# FSStation.net
KiCad netlist of a schematic drawn in EAGLE
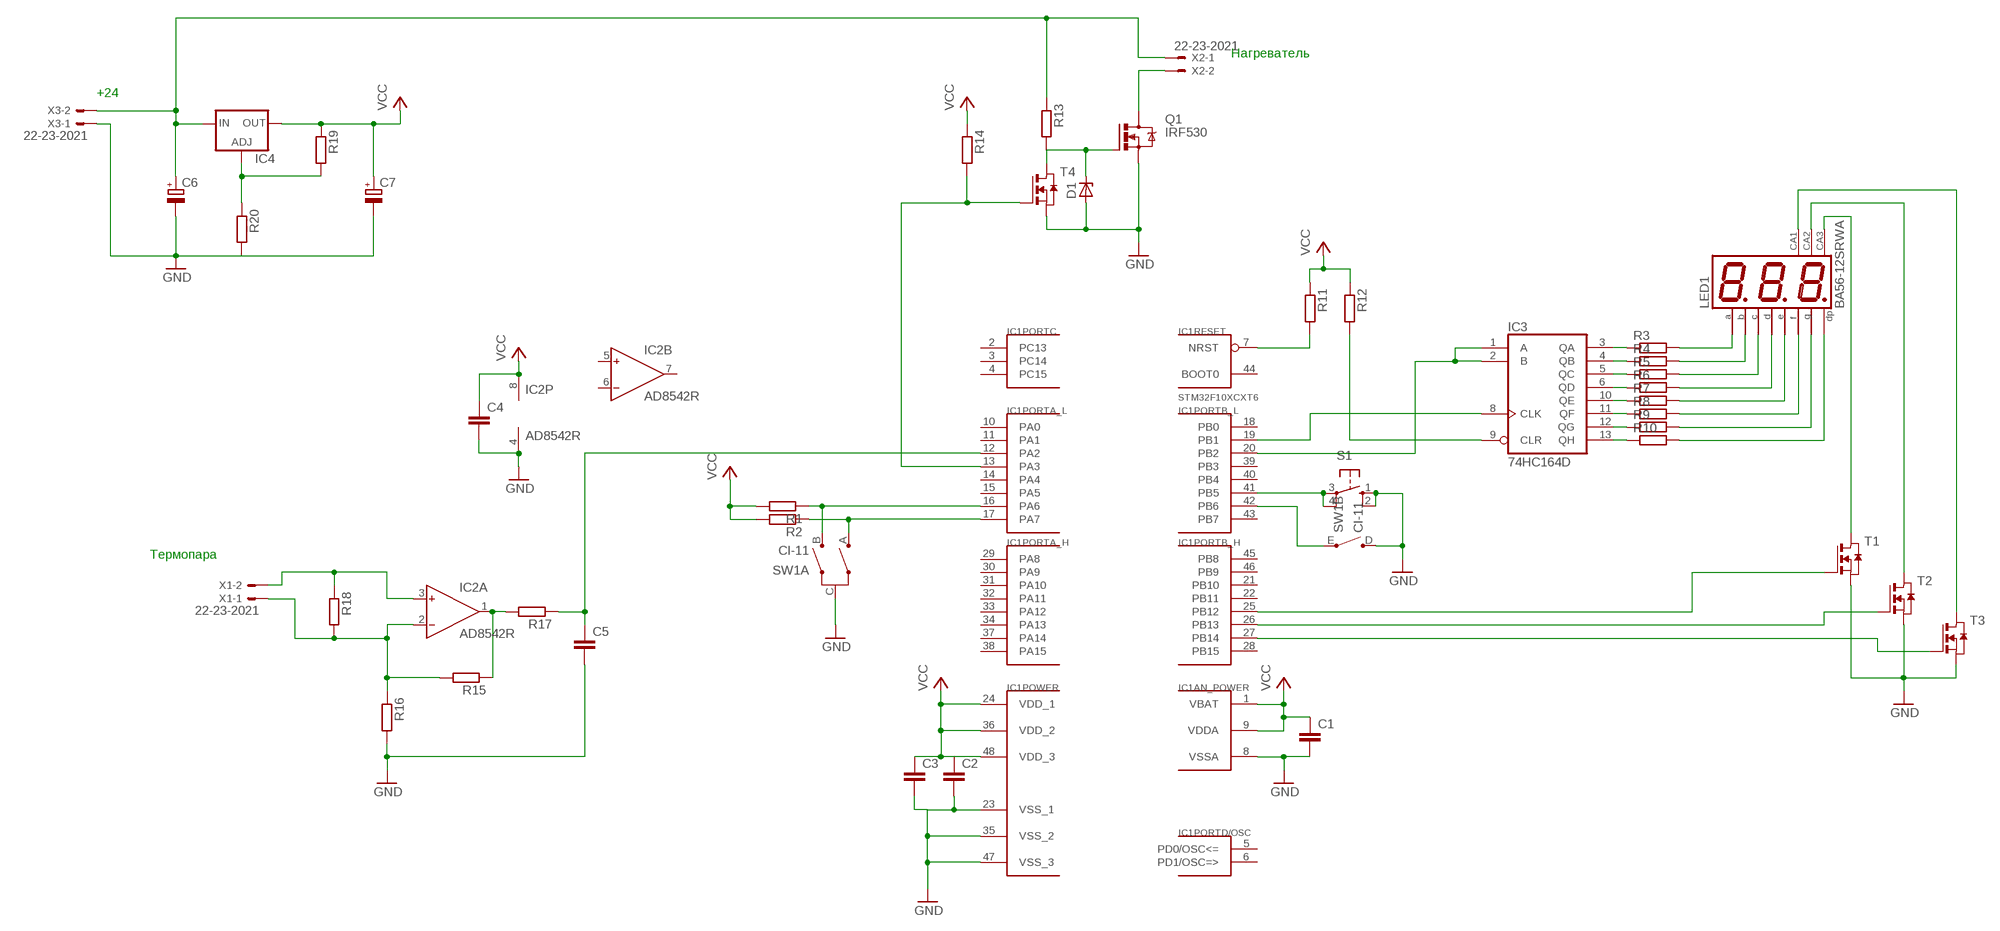
[diagram p0: schematic, sheet 1]

(export (version "E")
  (design (tool "Eeschema 10.0.6"))
  (components
    (comp (ref "C1")
      (value "C-EUC0805")
      (footprint "eagle-import:C0805")
      (libsource (lib "eagle-import") (part "C-EUC0805"))
    )
    (comp (ref "C2")
      (value "C-EUC0805")
      (footprint "eagle-import:C0805")
      (libsource (lib "eagle-import") (part "C-EUC0805"))
    )
    (comp (ref "C3")
      (value "C-EUC0805")
      (footprint "eagle-import:C0805")
      (libsource (lib "eagle-import") (part "C-EUC0805"))
    )
    (comp (ref "C4")
      (value "C-EUC0805")
      (footprint "eagle-import:C0805")
      (libsource (lib "eagle-import") (part "C-EUC0805"))
    )
    (comp (ref "C5")
      (value "C-EUC0805")
      (footprint "eagle-import:C0805")
      (libsource (lib "eagle-import") (part "C-EUC0805"))
    )
    (comp (ref "C6")
      (value "CPOL-EUE2.5-5")
      (footprint "eagle-import:E2,5-5")
      (libsource (lib "eagle-import") (part "CPOL-EUE2.5-5"))
    )
    (comp (ref "C7")
      (value "CPOL-EUE2.5-5")
      (footprint "eagle-import:E2,5-5")
      (libsource (lib "eagle-import") (part "CPOL-EUE2.5-5"))
    )
    (comp (ref "D1")
      (value "ZENER-DIODEDO34-7")
      (footprint "eagle-import:DO34Z7")
      (libsource (lib "eagle-import") (part "ZENER-DIODEDO34-7"))
    )
    (comp (ref "IC1")
      (value "STM32F10XCXT6")
      (footprint "eagle-import:TQFP48")
      (libsource (lib "eagle-import") (part "STM32F10XCXT6"))
    )
    (comp (ref "IC2")
      (value "AD8542R")
      (footprint "eagle-import:SO8")
      (fields (field (name "MF") "ALTERA CORPORATION") (field (name "MPN") "AD8542ARZ-REEL"))
      (libsource (lib "eagle-import") (part "AD8542R"))
    )
    (comp (ref "IC3")
      (value "74HC164D")
      (footprint "eagle-import:SO14")
      (libsource (lib "eagle-import") (part "74164DHC"))
    )
    (comp (ref "IC4")
      (value "LM317TS")
      (footprint "eagle-import:317TS")
      (libsource (lib "eagle-import") (part "LM317TS"))
    )
    (comp (ref "LED1")
      (value "BA56-12SRWA")
      (footprint "eagle-import:BX56-12")
      (libsource (lib "eagle-import") (part "B?56-12WAASR"))
    )
    (comp (ref "Q1")
      (value "IRF530")
      (footprint "eagle-import:TO220BV")
      (libsource (lib "eagle-import") (part "IRF530"))
    )
    (comp (ref "R1")
      (value "R-EU_R0805")
      (footprint "eagle-import:R0805")
      (libsource (lib "eagle-import") (part "R-EU_R0805"))
    )
    (comp (ref "R2")
      (value "R-EU_R0805")
      (footprint "eagle-import:R0805")
      (libsource (lib "eagle-import") (part "R-EU_R0805"))
    )
    (comp (ref "R3")
      (value "R-EU_R0805")
      (footprint "eagle-import:R0805")
      (libsource (lib "eagle-import") (part "R-EU_R0805"))
    )
    (comp (ref "R4")
      (value "R-EU_R0805")
      (footprint "eagle-import:R0805")
      (libsource (lib "eagle-import") (part "R-EU_R0805"))
    )
    (comp (ref "R5")
      (value "R-EU_R0805")
      (footprint "eagle-import:R0805")
      (libsource (lib "eagle-import") (part "R-EU_R0805"))
    )
    (comp (ref "R6")
      (value "R-EU_R0805")
      (footprint "eagle-import:R0805")
      (libsource (lib "eagle-import") (part "R-EU_R0805"))
    )
    (comp (ref "R7")
      (value "R-EU_R0805")
      (footprint "eagle-import:R0805")
      (libsource (lib "eagle-import") (part "R-EU_R0805"))
    )
    (comp (ref "R8")
      (value "R-EU_R0805")
      (footprint "eagle-import:R0805")
      (libsource (lib "eagle-import") (part "R-EU_R0805"))
    )
    (comp (ref "R9")
      (value "R-EU_R0805")
      (footprint "eagle-import:R0805")
      (libsource (lib "eagle-import") (part "R-EU_R0805"))
    )
    (comp (ref "R10")
      (value "R-EU_R0805")
      (footprint "eagle-import:R0805")
      (libsource (lib "eagle-import") (part "R-EU_R0805"))
    )
    (comp (ref "R11")
      (value "R-EU_R0805")
      (footprint "eagle-import:R0805")
      (libsource (lib "eagle-import") (part "R-EU_R0805"))
    )
    (comp (ref "R12")
      (value "R-EU_R0805")
      (footprint "eagle-import:R0805")
      (libsource (lib "eagle-import") (part "R-EU_R0805"))
    )
    (comp (ref "R13")
      (value "R-EU_R0805")
      (footprint "eagle-import:R0805")
      (libsource (lib "eagle-import") (part "R-EU_R0805"))
    )
    (comp (ref "R14")
      (value "R-EU_R0805")
      (footprint "eagle-import:R0805")
      (libsource (lib "eagle-import") (part "R-EU_R0805"))
    )
    (comp (ref "R15")
      (value "R-EU_R0805")
      (footprint "eagle-import:R0805")
      (libsource (lib "eagle-import") (part "R-EU_R0805"))
    )
    (comp (ref "R16")
      (value "R-EU_R0805")
      (footprint "eagle-import:R0805")
      (libsource (lib "eagle-import") (part "R-EU_R0805"))
    )
    (comp (ref "R17")
      (value "R-EU_R0805")
      (footprint "eagle-import:R0805")
      (libsource (lib "eagle-import") (part "R-EU_R0805"))
    )
    (comp (ref "R18")
      (value "R-EU_R0805")
      (footprint "eagle-import:R0805")
      (libsource (lib "eagle-import") (part "R-EU_R0805"))
    )
    (comp (ref "R19")
      (value "R-EU_R0805")
      (footprint "eagle-import:R0805")
      (libsource (lib "eagle-import") (part "R-EU_R0805"))
    )
    (comp (ref "R20")
      (value "R-EU_R0805")
      (footprint "eagle-import:R0805")
      (libsource (lib "eagle-import") (part "R-EU_R0805"))
    )
    (comp (ref "S1")
      (value "40-XX")
      (footprint "eagle-import:B3F-40XX")
      (fields (field (name "MF") "OMRON COMPONENTS USA") (field (name "MPN") "B3F-4000"))
      (libsource (lib "eagle-import") (part "40-XX"))
    )
    (comp (ref "SW1")
      (value "CI-11")
      (footprint "eagle-import:CI-11")
      (libsource (lib "eagle-import") (part "CI-11"))
    )
    (comp (ref "T1")
      (value "NMOSSOT23")
      (footprint "eagle-import:SOT-23")
      (libsource (lib "eagle-import") (part "NMOSSOT23"))
    )
    (comp (ref "T2")
      (value "NMOSSOT23")
      (footprint "eagle-import:SOT-23")
      (libsource (lib "eagle-import") (part "NMOSSOT23"))
    )
    (comp (ref "T3")
      (value "NMOSSOT23")
      (footprint "eagle-import:SOT-23")
      (libsource (lib "eagle-import") (part "NMOSSOT23"))
    )
    (comp (ref "T4")
      (value "NMOSSOT23")
      (footprint "eagle-import:SOT-23")
      (libsource (lib "eagle-import") (part "NMOSSOT23"))
    )
    (comp (ref "X1")
      (value "22-23-2021")
      (footprint "eagle-import:22-23-2021")
      (fields (field (name "MF") "MOLEX"))
      (libsource (lib "eagle-import") (part "22-23-2021"))
    )
    (comp (ref "X2")
      (value "22-23-2021")
      (footprint "eagle-import:22-23-2021")
      (fields (field (name "MF") "MOLEX"))
      (libsource (lib "eagle-import") (part "22-23-2021"))
    )
    (comp (ref "X3")
      (value "22-23-2021")
      (footprint "eagle-import:22-23-2021")
      (fields (field (name "MF") "MOLEX"))
      (libsource (lib "eagle-import") (part "22-23-2021"))
    )
  )
  (nets
    (net (code "1") (name "GND") (class "Default")
      (node (ref "C1") (pin "2") (pinfunction "2_2") (pintype "passive"))
      (node (ref "C2") (pin "2") (pinfunction "2_2") (pintype "passive"))
      (node (ref "C3") (pin "2") (pinfunction "2_2") (pintype "passive"))
      (node (ref "C4") (pin "2") (pinfunction "2_2") (pintype "passive"))
      (node (ref "C5") (pin "2") (pinfunction "2_2") (pintype "passive"))
      (node (ref "C6") (pin "-") (pinfunction "-_-") (pintype "passive"))
      (node (ref "C7") (pin "-") (pinfunction "-_-") (pintype "passive"))
      (node (ref "D1") (pin "A") (pinfunction "A_A") (pintype "passive"))
      (node (ref "IC1") (pin "23") (pinfunction "VSS_1_23") (pintype "power_in"))
      (node (ref "IC1") (pin "35") (pinfunction "VSS_2_35") (pintype "power_in"))
      (node (ref "IC1") (pin "47") (pinfunction "VSS_3_47") (pintype "power_in"))
      (node (ref "IC1") (pin "8") (pinfunction "VSSA_8") (pintype "power_in"))
      (node (ref "IC2") (pin "4") (pinfunction "V-_4") (pintype "power_in"))
      (node (ref "Q1") (pin "S") (pinfunction "S_S") (pintype "passive"))
      (node (ref "R16") (pin "2") (pinfunction "2_2") (pintype "passive"))
      (node (ref "R20") (pin "2") (pinfunction "2_2") (pintype "passive"))
      (node (ref "S1") (pin "1") (pinfunction "S_1") (pintype "passive"))
      (node (ref "S1") (pin "2") (pinfunction "S1_2") (pintype "passive"))
      (node (ref "SW1") (pin "C") (pinfunction "C_C") (pintype "passive"))
      (node (ref "SW1") (pin "D") (pinfunction "D_D") (pintype "passive"))
      (node (ref "T1") (pin "2") (pinfunction "S_2") (pintype "passive"))
      (node (ref "T2") (pin "2") (pinfunction "S_2") (pintype "passive"))
      (node (ref "T3") (pin "2") (pinfunction "S_2") (pintype "passive"))
      (node (ref "T4") (pin "2") (pinfunction "S_2") (pintype "passive"))
      (node (ref "X3") (pin "1") (pinfunction "S_1") (pintype "passive"))
    )
    (net (code "2") (name "Net-(IC1C-PA2)") (class "Default")
      (node (ref "C5") (pin "1") (pinfunction "1_1") (pintype "passive"))
      (node (ref "IC1") (pin "12") (pinfunction "PA2_12") (pintype "bidirectional"))
      (node (ref "R17") (pin "1") (pinfunction "1_1") (pintype "passive"))
    )
    (net (code "3") (name "Net-(IC1C-PA3)") (class "Default")
      (node (ref "IC1") (pin "13") (pinfunction "PA3_13") (pintype "bidirectional"))
      (node (ref "R14") (pin "2") (pinfunction "2_2") (pintype "passive"))
      (node (ref "T4") (pin "3") (pinfunction "G_3") (pintype "passive"))
    )
    (net (code "4") (name "Net-(IC1C-PA6)") (class "Default")
      (node (ref "IC1") (pin "16") (pinfunction "PA6_16") (pintype "bidirectional"))
      (node (ref "R1") (pin "1") (pinfunction "1_1") (pintype "passive"))
      (node (ref "SW1") (pin "B") (pinfunction "B_B") (pintype "passive"))
    )
    (net (code "5") (name "Net-(IC1C-PA7)") (class "Default")
      (node (ref "IC1") (pin "17") (pinfunction "PA7_17") (pintype "bidirectional"))
      (node (ref "R2") (pin "1") (pinfunction "1_1") (pintype "passive"))
      (node (ref "SW1") (pin "A") (pinfunction "A_A") (pintype "passive"))
    )
    (net (code "6") (name "Net-(IC1D-PB12)") (class "Default")
      (node (ref "IC1") (pin "25") (pinfunction "PB12_25") (pintype "bidirectional"))
      (node (ref "T1") (pin "3") (pinfunction "G_3") (pintype "passive"))
    )
    (net (code "7") (name "Net-(IC1D-PB13)") (class "Default")
      (node (ref "IC1") (pin "26") (pinfunction "PB13_26") (pintype "bidirectional"))
      (node (ref "T2") (pin "3") (pinfunction "G_3") (pintype "passive"))
    )
    (net (code "8") (name "Net-(IC1D-PB14)") (class "Default")
      (node (ref "IC1") (pin "27") (pinfunction "PB14_27") (pintype "bidirectional"))
      (node (ref "T3") (pin "3") (pinfunction "G_3") (pintype "passive"))
    )
    (net (code "9") (name "Net-(IC1E-PB1)") (class "Default")
      (node (ref "IC1") (pin "19") (pinfunction "PB1_19") (pintype "bidirectional"))
      (node (ref "IC3") (pin "8") (pinfunction "CLK_8") (pintype "input"))
    )
    (net (code "10") (name "Net-(IC1E-PB2)") (class "Default")
      (node (ref "IC1") (pin "20") (pinfunction "PB2_20") (pintype "bidirectional"))
      (node (ref "IC3") (pin "1") (pinfunction "A_1") (pintype "input"))
      (node (ref "IC3") (pin "2") (pinfunction "B_2") (pintype "input"))
    )
    (net (code "11") (name "Net-(IC1E-PB5)") (class "Default")
      (node (ref "IC1") (pin "41") (pinfunction "PB5_41") (pintype "bidirectional"))
      (node (ref "S1") (pin "3") (pinfunction "P_3") (pintype "passive"))
      (node (ref "S1") (pin "4") (pinfunction "P1_4") (pintype "passive"))
    )
    (net (code "12") (name "Net-(IC1E-PB6)") (class "Default")
      (node (ref "IC1") (pin "42") (pinfunction "PB6_42") (pintype "bidirectional"))
      (node (ref "SW1") (pin "E") (pinfunction "E_E") (pintype "passive"))
    )
    (net (code "13") (name "Net-(IC1I-NRST)") (class "Default")
      (node (ref "IC1") (pin "7") (pinfunction "NRST_7") (pintype "input"))
      (node (ref "R11") (pin "2") (pinfunction "2_2") (pintype "passive"))
    )
    (net (code "14") (name "Net-(IC2A-IN+)") (class "Default")
      (node (ref "IC2") (pin "3") (pinfunction "IN+_3") (pintype "input"))
      (node (ref "R18") (pin "1") (pinfunction "1_1") (pintype "passive"))
      (node (ref "X1") (pin "2") (pinfunction "S_2") (pintype "passive"))
    )
    (net (code "15") (name "Net-(IC2A-IN-)") (class "Default")
      (node (ref "IC2") (pin "2") (pinfunction "IN-_2") (pintype "input"))
      (node (ref "R15") (pin "2") (pinfunction "2_2") (pintype "passive"))
      (node (ref "R16") (pin "1") (pinfunction "1_1") (pintype "passive"))
      (node (ref "R18") (pin "2") (pinfunction "2_2") (pintype "passive"))
      (node (ref "X1") (pin "1") (pinfunction "S_1") (pintype "passive"))
    )
    (net (code "16") (name "Net-(IC2A-OUT)") (class "Default")
      (node (ref "IC2") (pin "1") (pinfunction "OUT_1") (pintype "output"))
      (node (ref "R15") (pin "1") (pinfunction "1_1") (pintype "passive"))
      (node (ref "R17") (pin "2") (pinfunction "2_2") (pintype "passive"))
    )
    (net (code "17") (name "Net-(IC3A-CLR)") (class "Default")
      (node (ref "IC3") (pin "9") (pinfunction "CLR_9") (pintype "input"))
      (node (ref "R12") (pin "2") (pinfunction "2_2") (pintype "passive"))
    )
    (net (code "18") (name "Net-(IC3A-QA)") (class "Default")
      (node (ref "IC3") (pin "3") (pinfunction "QA_3") (pintype "output"))
      (node (ref "R3") (pin "1") (pinfunction "1_1") (pintype "passive"))
    )
    (net (code "19") (name "Net-(IC3A-QB)") (class "Default")
      (node (ref "IC3") (pin "4") (pinfunction "QB_4") (pintype "output"))
      (node (ref "R4") (pin "1") (pinfunction "1_1") (pintype "passive"))
    )
    (net (code "20") (name "Net-(IC3A-QC)") (class "Default")
      (node (ref "IC3") (pin "5") (pinfunction "QC_5") (pintype "output"))
      (node (ref "R5") (pin "1") (pinfunction "1_1") (pintype "passive"))
    )
    (net (code "21") (name "Net-(IC3A-QD)") (class "Default")
      (node (ref "IC3") (pin "6") (pinfunction "QD_6") (pintype "output"))
      (node (ref "R6") (pin "1") (pinfunction "1_1") (pintype "passive"))
    )
    (net (code "22") (name "Net-(IC3A-QE)") (class "Default")
      (node (ref "IC3") (pin "10") (pinfunction "QE_10") (pintype "output"))
      (node (ref "R7") (pin "1") (pinfunction "1_1") (pintype "passive"))
    )
    (net (code "23") (name "Net-(IC3A-QF)") (class "Default")
      (node (ref "IC3") (pin "11") (pinfunction "QF_11") (pintype "output"))
      (node (ref "R8") (pin "1") (pinfunction "1_1") (pintype "passive"))
    )
    (net (code "24") (name "Net-(IC3A-QG)") (class "Default")
      (node (ref "IC3") (pin "12") (pinfunction "QG_12") (pintype "output"))
      (node (ref "R9") (pin "1") (pinfunction "1_1") (pintype "passive"))
    )
    (net (code "25") (name "Net-(IC3A-QH)") (class "Default")
      (node (ref "IC3") (pin "13") (pinfunction "QH_13") (pintype "output"))
      (node (ref "R10") (pin "1") (pinfunction "1_1") (pintype "passive"))
    )
    (net (code "26") (name "Net-(IC4-ADJ)") (class "Default")
      (node (ref "IC4") (pin "1") (pinfunction "ADJ_1") (pintype "input"))
      (node (ref "R19") (pin "2") (pinfunction "2_2") (pintype "passive"))
      (node (ref "R20") (pin "1") (pinfunction "1_1") (pintype "passive"))
    )
    (net (code "27") (name "Net-(IC4-IN)") (class "Default")
      (node (ref "C6") (pin "+") (pinfunction "+_+") (pintype "passive"))
      (node (ref "IC4") (pin "3") (pinfunction "IN_3") (pintype "input"))
      (node (ref "R13") (pin "1") (pinfunction "1_1") (pintype "passive"))
      (node (ref "X2") (pin "1") (pinfunction "S_1") (pintype "passive"))
      (node (ref "X3") (pin "2") (pinfunction "S_2") (pintype "passive"))
    )
    (net (code "28") (name "Net-(LED1-A)") (class "Default")
      (node (ref "LED1") (pin "11") (pinfunction "A_11") (pintype "passive"))
      (node (ref "R3") (pin "2") (pinfunction "2_2") (pintype "passive"))
    )
    (net (code "29") (name "Net-(LED1-B)") (class "Default")
      (node (ref "LED1") (pin "7") (pinfunction "B_7") (pintype "passive"))
      (node (ref "R4") (pin "2") (pinfunction "2_2") (pintype "passive"))
    )
    (net (code "30") (name "Net-(LED1-C)") (class "Default")
      (node (ref "LED1") (pin "4") (pinfunction "C_4") (pintype "passive"))
      (node (ref "R5") (pin "2") (pinfunction "2_2") (pintype "passive"))
    )
    (net (code "31") (name "Net-(LED1-D)") (class "Default")
      (node (ref "LED1") (pin "2") (pinfunction "D_2") (pintype "passive"))
      (node (ref "R6") (pin "2") (pinfunction "2_2") (pintype "passive"))
    )
    (net (code "32") (name "Net-(LED1-DP)") (class "Default")
      (node (ref "LED1") (pin "3") (pinfunction "DP_3") (pintype "passive"))
      (node (ref "R10") (pin "2") (pinfunction "2_2") (pintype "passive"))
    )
    (net (code "33") (name "Net-(LED1-E)") (class "Default")
      (node (ref "LED1") (pin "1") (pinfunction "E_1") (pintype "passive"))
      (node (ref "R7") (pin "2") (pinfunction "2_2") (pintype "passive"))
    )
    (net (code "34") (name "Net-(LED1-F)") (class "Default")
      (node (ref "LED1") (pin "10") (pinfunction "F_10") (pintype "passive"))
      (node (ref "R8") (pin "2") (pinfunction "2_2") (pintype "passive"))
    )
    (net (code "35") (name "Net-(LED1-G)") (class "Default")
      (node (ref "LED1") (pin "5") (pinfunction "G_5") (pintype "passive"))
      (node (ref "R9") (pin "2") (pinfunction "2_2") (pintype "passive"))
    )
    (net (code "36") (name "Net-(T1-D)") (class "Default")
      (node (ref "LED1") (pin "8") (pinfunction "CA_8") (pintype "passive"))
      (node (ref "T1") (pin "1") (pinfunction "D_1") (pintype "passive"))
    )
    (net (code "37") (name "Net-(T2-D)") (class "Default")
      (node (ref "LED1") (pin "9") (pinfunction "CA_9") (pintype "passive"))
      (node (ref "T2") (pin "1") (pinfunction "D_1") (pintype "passive"))
    )
    (net (code "38") (name "Net-(T3-D)") (class "Default")
      (node (ref "LED1") (pin "12") (pinfunction "CA_12") (pintype "passive"))
      (node (ref "T3") (pin "1") (pinfunction "D_1") (pintype "passive"))
    )
    (net (code "39") (name "Net-(T4-D)") (class "Default")
      (node (ref "D1") (pin "C") (pinfunction "C_C") (pintype "passive"))
      (node (ref "Q1") (pin "G") (pinfunction "G_G") (pintype "passive"))
      (node (ref "R13") (pin "2") (pinfunction "2_2") (pintype "passive"))
      (node (ref "T4") (pin "1") (pinfunction "D_1") (pintype "passive"))
    )
    (net (code "40") (name "Net-(X2B-S)") (class "Default")
      (node (ref "Q1") (pin "D") (pinfunction "D_D") (pintype "passive"))
      (node (ref "X2") (pin "2") (pinfunction "S_2") (pintype "passive"))
    )
    (net (code "41") (name "VCC") (class "Default")
      (node (ref "C1") (pin "1") (pinfunction "1_1") (pintype "passive"))
      (node (ref "C3") (pin "1") (pinfunction "1_1") (pintype "passive"))
      (node (ref "C4") (pin "1") (pinfunction "1_1") (pintype "passive"))
      (node (ref "C7") (pin "+") (pinfunction "+_+") (pintype "passive"))
      (node (ref "IC1") (pin "1") (pinfunction "VBAT_1") (pintype "power_in"))
      (node (ref "IC1") (pin "24") (pinfunction "VDD_1_24") (pintype "power_in"))
      (node (ref "IC1") (pin "36") (pinfunction "VDD_2_36") (pintype "power_in"))
      (node (ref "IC1") (pin "48") (pinfunction "VDD_3_48") (pintype "power_in"))
      (node (ref "IC1") (pin "9") (pinfunction "VDDA_9") (pintype "power_in"))
      (node (ref "IC2") (pin "8") (pinfunction "V+_8") (pintype "power_in"))
      (node (ref "IC4") (pin "2") (pinfunction "OUT_2") (pintype "passive"))
      (node (ref "R1") (pin "2") (pinfunction "2_2") (pintype "passive"))
      (node (ref "R11") (pin "1") (pinfunction "1_1") (pintype "passive"))
      (node (ref "R12") (pin "1") (pinfunction "1_1") (pintype "passive"))
      (node (ref "R14") (pin "1") (pinfunction "1_1") (pintype "passive"))
      (node (ref "R19") (pin "1") (pinfunction "1_1") (pintype "passive"))
      (node (ref "R2") (pin "2") (pinfunction "2_2") (pintype "passive"))
    )
    (net (code "42") (name "unconnected-(C2-Pad1)") (class "Default")
      (node (ref "C2") (pin "1") (pinfunction "1_1") (pintype "passive"))
    )
    (net (code "43") (name "unconnected-(IC1B-PA8-Pad29)") (class "Default")
      (node (ref "IC1") (pin "29") (pinfunction "PA8_29") (pintype "bidirectional"))
    )
    (net (code "44") (name "unconnected-(IC1B-PA9-Pad30)") (class "Default")
      (node (ref "IC1") (pin "30") (pinfunction "PA9_30") (pintype "bidirectional"))
    )
    (net (code "45") (name "unconnected-(IC1B-PA10-Pad31)") (class "Default")
      (node (ref "IC1") (pin "31") (pinfunction "PA10_31") (pintype "bidirectional"))
    )
    (net (code "46") (name "unconnected-(IC1B-PA11-Pad32)") (class "Default")
      (node (ref "IC1") (pin "32") (pinfunction "PA11_32") (pintype "bidirectional"))
    )
    (net (code "47") (name "unconnected-(IC1B-PA12-Pad33)") (class "Default")
      (node (ref "IC1") (pin "33") (pinfunction "PA12_33") (pintype "bidirectional"))
    )
    (net (code "48") (name "unconnected-(IC1B-PA13-Pad34)") (class "Default")
      (node (ref "IC1") (pin "34") (pinfunction "PA13_34") (pintype "bidirectional"))
    )
    (net (code "49") (name "unconnected-(IC1B-PA14-Pad37)") (class "Default")
      (node (ref "IC1") (pin "37") (pinfunction "PA14_37") (pintype "bidirectional"))
    )
    (net (code "50") (name "unconnected-(IC1B-PA15-Pad38)") (class "Default")
      (node (ref "IC1") (pin "38") (pinfunction "PA15_38") (pintype "bidirectional"))
    )
    (net (code "51") (name "unconnected-(IC1C-PA0-Pad10)") (class "Default")
      (node (ref "IC1") (pin "10") (pinfunction "PA0_10") (pintype "bidirectional"))
    )
    (net (code "52") (name "unconnected-(IC1C-PA1-Pad11)") (class "Default")
      (node (ref "IC1") (pin "11") (pinfunction "PA1_11") (pintype "bidirectional"))
    )
    (net (code "53") (name "unconnected-(IC1C-PA4-Pad14)") (class "Default")
      (node (ref "IC1") (pin "14") (pinfunction "PA4_14") (pintype "bidirectional"))
    )
    (net (code "54") (name "unconnected-(IC1C-PA5-Pad15)") (class "Default")
      (node (ref "IC1") (pin "15") (pinfunction "PA5_15") (pintype "bidirectional"))
    )
    (net (code "55") (name "unconnected-(IC1D-PB8-Pad45)") (class "Default")
      (node (ref "IC1") (pin "45") (pinfunction "PB8_45") (pintype "bidirectional"))
    )
    (net (code "56") (name "unconnected-(IC1D-PB9-Pad46)") (class "Default")
      (node (ref "IC1") (pin "46") (pinfunction "PB9_46") (pintype "bidirectional"))
    )
    (net (code "57") (name "unconnected-(IC1D-PB10-Pad21)") (class "Default")
      (node (ref "IC1") (pin "21") (pinfunction "PB10_21") (pintype "bidirectional"))
    )
    (net (code "58") (name "unconnected-(IC1D-PB11-Pad22)") (class "Default")
      (node (ref "IC1") (pin "22") (pinfunction "PB11_22") (pintype "bidirectional"))
    )
    (net (code "59") (name "unconnected-(IC1D-PB15-Pad28)") (class "Default")
      (node (ref "IC1") (pin "28") (pinfunction "PB15_28") (pintype "bidirectional"))
    )
    (net (code "60") (name "unconnected-(IC1E-PB0-Pad18)") (class "Default")
      (node (ref "IC1") (pin "18") (pinfunction "PB0_18") (pintype "bidirectional"))
    )
    (net (code "61") (name "unconnected-(IC1E-PB3-Pad39)") (class "Default")
      (node (ref "IC1") (pin "39") (pinfunction "PB3_39") (pintype "bidirectional"))
    )
    (net (code "62") (name "unconnected-(IC1E-PB4-Pad40)") (class "Default")
      (node (ref "IC1") (pin "40") (pinfunction "PB4_40") (pintype "bidirectional"))
    )
    (net (code "63") (name "unconnected-(IC1E-PB7-Pad43)") (class "Default")
      (node (ref "IC1") (pin "43") (pinfunction "PB7_43") (pintype "bidirectional"))
    )
    (net (code "64") (name "unconnected-(IC1F-PC13-Pad2)") (class "Default")
      (node (ref "IC1") (pin "2") (pinfunction "PC13_2") (pintype "bidirectional"))
    )
    (net (code "65") (name "unconnected-(IC1F-PC14-Pad3)") (class "Default")
      (node (ref "IC1") (pin "3") (pinfunction "PC14_3") (pintype "bidirectional"))
    )
    (net (code "66") (name "unconnected-(IC1F-PC15-Pad4)") (class "Default")
      (node (ref "IC1") (pin "4") (pinfunction "PC15_4") (pintype "bidirectional"))
    )
    (net (code "67") (name "unconnected-(IC1G-PD0{slash}OSC<=-Pad5)") (class "Default")
      (node (ref "IC1") (pin "5") (pinfunction "PD0/OSC<=_5") (pintype "bidirectional"))
    )
    (net (code "68") (name "unconnected-(IC1G-PD1{slash}OSC=>-Pad6)") (class "Default")
      (node (ref "IC1") (pin "6") (pinfunction "PD1/OSC=>_6") (pintype "bidirectional"))
    )
    (net (code "69") (name "unconnected-(IC1I-BOOT0-Pad44)") (class "Default")
      (node (ref "IC1") (pin "44") (pinfunction "BOOT0_44") (pintype "input"))
    )
    (net (code "70") (name "unconnected-(IC2B-IN+-Pad5)") (class "Default")
      (node (ref "IC2") (pin "5") (pinfunction "IN+_5") (pintype "input"))
    )
    (net (code "71") (name "unconnected-(IC2B-IN--Pad6)") (class "Default")
      (node (ref "IC2") (pin "6") (pinfunction "IN-_6") (pintype "input"))
    )
    (net (code "72") (name "unconnected-(IC2B-OUT-Pad7)") (class "Default")
      (node (ref "IC2") (pin "7") (pinfunction "OUT_7") (pintype "output"))
    )
  )
)
